# legacy-main.net
KiCad netlist of a schematic drawn in Altium Designer
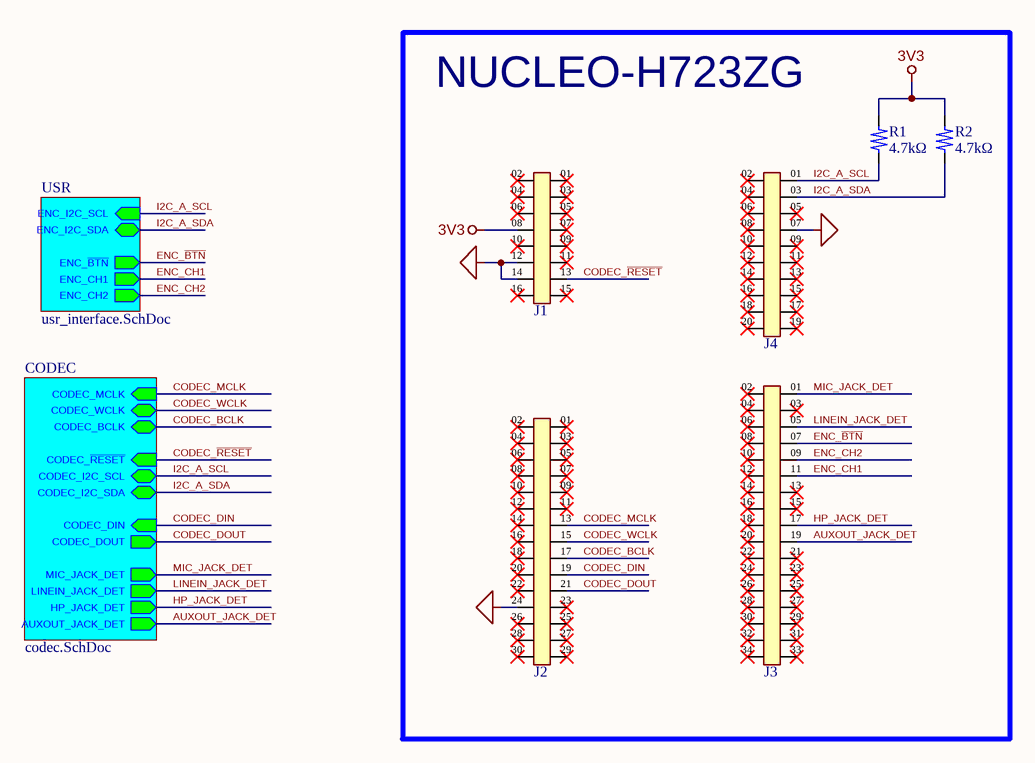
[diagram p0: legacy-main.SchDoc]

(export (version "E")
  (design (tool "Eeschema 10.0.6"))
  (components
    (comp (ref "J1")
      (value "TSW-108-07-G-D")
      (footprint "SAMTEC_TSW-108-07-G-D")
      (description "Pin Header, Unshrouded, Board-to-Board, 2.54 mm, 2 Rows, 16 Contacts, Through Hole, TSW")
      (libsource (lib "Connectors") (part "TSW-108-07-G-D"))
    )
    (comp (ref "J2")
      (value "TSW-115-07-G-D")
      (footprint "SAMTEC_TSW-115-07-G-D")
      (description "Conn, Header, 30Pos, 2Row, 2.54Mm Rohs Compliant: Yes ¦Samtec, Inc. TSW-115-07-G-D")
      (libsource (lib "Connectors") (part "TSW-115-07-G-D"))
    )
    (comp (ref "J3")
      (value "TSW-117-07-G-D-LL")
      (footprint "SAMTEC_TSW-117-07-G-D-LL")
      (description "Pin Header, Board-to-Board, 2.54 mm, 2 Rows, 34 Contacts, Through Hole, TSW Series")
      (libsource (lib "Connectors") (part "TSW-117-07-G-D-LL"))
    )
    (comp (ref "J4")
      (value "TSW-110-07-G-D")
      (footprint "SAMTEC_TSW-110-07-G-D")
      (description "Pin Header, Vertical, Board-to-Board, 2.54 mm, 2 Rows, 20 Contacts, Through Hole, HTSW Series")
      (libsource (lib "Connectors") (part "TSW-110-07-G-D"))
    )
    (comp (ref "R1")
      (value "4.7kΩ")
      (footprint "RESC2012")
      (description "125Mw Thick Film Resistors 100Ppm/ 1% 4.7K 0805 Chip Resistor Surface Mount Rohs")
      (fields
        (field (name "MANUFACTURER") "YAGEO")
        (field (name "MANUFACTURER PART NUMBER") "RC0805FR-074K7L")
      )
      (libsource (lib "Resistors") (part "RC0805FR-074K7L"))
    )
    (comp (ref "R2")
      (value "4.7kΩ")
      (footprint "RESC2012")
      (description "125Mw Thick Film Resistors 100Ppm/ 1% 4.7K 0805 Chip Resistor Surface Mount Rohs")
      (fields
        (field (name "MANUFACTURER") "YAGEO")
        (field (name "MANUFACTURER PART NUMBER") "RC0805FR-074K7L")
      )
      (libsource (lib "Resistors") (part "RC0805FR-074K7L"))
    )
  )
  (nets
    (net (code "1") (name "/AUXOUT_JACK_DET") (class "Default")
      (node (ref "J3") (pin "19") (pinfunction "19_19") (pintype "passive"))
    )
    (net (code "2") (name "/CODEC_BCLK") (class "Default")
      (node (ref "J2") (pin "17") (pinfunction "17_17") (pintype "passive"))
    )
    (net (code "3") (name "/CODEC_DIN") (class "Default")
      (node (ref "J2") (pin "19") (pinfunction "19_19") (pintype "passive"))
    )
    (net (code "4") (name "/CODEC_DOUT") (class "Default")
      (node (ref "J2") (pin "21") (pinfunction "21_21") (pintype "passive"))
    )
    (net (code "5") (name "/CODEC_MCLK") (class "Default")
      (node (ref "J2") (pin "13") (pinfunction "13_13") (pintype "passive"))
    )
    (net (code "6") (name "/CODEC_WCLK") (class "Default")
      (node (ref "J2") (pin "15") (pinfunction "15_15") (pintype "passive"))
    )
    (net (code "7") (name "/CODEC_~{RESET}") (class "Default")
      (node (ref "J1") (pin "13") (pinfunction "13_13") (pintype "passive"))
    )
    (net (code "8") (name "/ENC_CH1") (class "Default")
      (node (ref "J3") (pin "11") (pinfunction "11_11") (pintype "passive"))
    )
    (net (code "9") (name "/ENC_CH2") (class "Default")
      (node (ref "J3") (pin "09") (pinfunction "09_09") (pintype "passive"))
    )
    (net (code "10") (name "/ENC_~{BTN}") (class "Default")
      (node (ref "J3") (pin "07") (pinfunction "07_07") (pintype "passive"))
    )
    (net (code "11") (name "/HP_JACK_DET") (class "Default")
      (node (ref "J3") (pin "17") (pinfunction "17_17") (pintype "passive"))
    )
    (net (code "12") (name "/I2C_A_SCL") (class "Default")
      (node (ref "J4") (pin "01") (pinfunction "01_01") (pintype "passive"))
      (node (ref "R1") (pin "1") (pinfunction "1_1") (pintype "passive"))
    )
    (net (code "13") (name "/I2C_A_SDA") (class "Default")
      (node (ref "J4") (pin "03") (pinfunction "03_03") (pintype "passive"))
      (node (ref "R2") (pin "1") (pinfunction "1_1") (pintype "passive"))
    )
    (net (code "14") (name "/LINEIN_JACK_DET") (class "Default")
      (node (ref "J3") (pin "05") (pinfunction "05_05") (pintype "passive"))
    )
    (net (code "15") (name "/MIC_JACK_DET") (class "Default")
      (node (ref "J3") (pin "01") (pinfunction "01_01") (pintype "passive"))
    )
    (net (code "16") (name "3V3") (class "Default")
      (node (ref "J1") (pin "08") (pinfunction "08_08") (pintype "passive"))
      (node (ref "R1") (pin "2") (pinfunction "2_2") (pintype "passive"))
      (node (ref "R2") (pin "2") (pinfunction "2_2") (pintype "passive"))
    )
    (net (code "17") (name "DGND") (class "Default")
      (node (ref "J1") (pin "12") (pinfunction "12_12") (pintype "passive"))
      (node (ref "J1") (pin "14") (pinfunction "14_14") (pintype "passive"))
      (node (ref "J2") (pin "24") (pinfunction "24_24") (pintype "passive"))
      (node (ref "J4") (pin "07") (pinfunction "07_07") (pintype "passive"))
    )
    (net (code "18") (name "unconnected-(J1-Pad01)") (class "Default")
      (node (ref "J1") (pin "01") (pinfunction "01_01") (pintype "passive+no_connect"))
    )
    (net (code "19") (name "unconnected-(J1-Pad02)") (class "Default")
      (node (ref "J1") (pin "02") (pinfunction "02_02") (pintype "passive+no_connect"))
    )
    (net (code "20") (name "unconnected-(J1-Pad03)") (class "Default")
      (node (ref "J1") (pin "03") (pinfunction "03_03") (pintype "passive+no_connect"))
    )
    (net (code "21") (name "unconnected-(J1-Pad04)") (class "Default")
      (node (ref "J1") (pin "04") (pinfunction "04_04") (pintype "passive+no_connect"))
    )
    (net (code "22") (name "unconnected-(J1-Pad05)") (class "Default")
      (node (ref "J1") (pin "05") (pinfunction "05_05") (pintype "passive+no_connect"))
    )
    (net (code "23") (name "unconnected-(J1-Pad06)") (class "Default")
      (node (ref "J1") (pin "06") (pinfunction "06_06") (pintype "passive+no_connect"))
    )
    (net (code "24") (name "unconnected-(J1-Pad07)") (class "Default")
      (node (ref "J1") (pin "07") (pinfunction "07_07") (pintype "passive+no_connect"))
    )
    (net (code "25") (name "unconnected-(J1-Pad09)") (class "Default")
      (node (ref "J1") (pin "09") (pinfunction "09_09") (pintype "passive+no_connect"))
    )
    (net (code "26") (name "unconnected-(J1-Pad10)") (class "Default")
      (node (ref "J1") (pin "10") (pinfunction "10_10") (pintype "passive+no_connect"))
    )
    (net (code "27") (name "unconnected-(J1-Pad11)") (class "Default")
      (node (ref "J1") (pin "11") (pinfunction "11_11") (pintype "passive+no_connect"))
    )
    (net (code "28") (name "unconnected-(J1-Pad15)") (class "Default")
      (node (ref "J1") (pin "15") (pinfunction "15_15") (pintype "passive+no_connect"))
    )
    (net (code "29") (name "unconnected-(J1-Pad16)") (class "Default")
      (node (ref "J1") (pin "16") (pinfunction "16_16") (pintype "passive+no_connect"))
    )
    (net (code "30") (name "unconnected-(J2-Pad01)") (class "Default")
      (node (ref "J2") (pin "01") (pinfunction "01_01") (pintype "passive+no_connect"))
    )
    (net (code "31") (name "unconnected-(J2-Pad02)") (class "Default")
      (node (ref "J2") (pin "02") (pinfunction "02_02") (pintype "passive+no_connect"))
    )
    (net (code "32") (name "unconnected-(J2-Pad03)") (class "Default")
      (node (ref "J2") (pin "03") (pinfunction "03_03") (pintype "passive+no_connect"))
    )
    (net (code "33") (name "unconnected-(J2-Pad04)") (class "Default")
      (node (ref "J2") (pin "04") (pinfunction "04_04") (pintype "passive+no_connect"))
    )
    (net (code "34") (name "unconnected-(J2-Pad05)") (class "Default")
      (node (ref "J2") (pin "05") (pinfunction "05_05") (pintype "passive+no_connect"))
    )
    (net (code "35") (name "unconnected-(J2-Pad06)") (class "Default")
      (node (ref "J2") (pin "06") (pinfunction "06_06") (pintype "passive+no_connect"))
    )
    (net (code "36") (name "unconnected-(J2-Pad07)") (class "Default")
      (node (ref "J2") (pin "07") (pinfunction "07_07") (pintype "passive+no_connect"))
    )
    (net (code "37") (name "unconnected-(J2-Pad08)") (class "Default")
      (node (ref "J2") (pin "08") (pinfunction "08_08") (pintype "passive+no_connect"))
    )
    (net (code "38") (name "unconnected-(J2-Pad09)") (class "Default")
      (node (ref "J2") (pin "09") (pinfunction "09_09") (pintype "passive+no_connect"))
    )
    (net (code "39") (name "unconnected-(J2-Pad10)") (class "Default")
      (node (ref "J2") (pin "10") (pinfunction "10_10") (pintype "passive+no_connect"))
    )
    (net (code "40") (name "unconnected-(J2-Pad11)") (class "Default")
      (node (ref "J2") (pin "11") (pinfunction "11_11") (pintype "passive+no_connect"))
    )
    (net (code "41") (name "unconnected-(J2-Pad12)") (class "Default")
      (node (ref "J2") (pin "12") (pinfunction "12_12") (pintype "passive+no_connect"))
    )
    (net (code "42") (name "unconnected-(J2-Pad14)") (class "Default")
      (node (ref "J2") (pin "14") (pinfunction "14_14") (pintype "passive+no_connect"))
    )
    (net (code "43") (name "unconnected-(J2-Pad16)") (class "Default")
      (node (ref "J2") (pin "16") (pinfunction "16_16") (pintype "passive+no_connect"))
    )
    (net (code "44") (name "unconnected-(J2-Pad18)") (class "Default")
      (node (ref "J2") (pin "18") (pinfunction "18_18") (pintype "passive+no_connect"))
    )
    (net (code "45") (name "unconnected-(J2-Pad20)") (class "Default")
      (node (ref "J2") (pin "20") (pinfunction "20_20") (pintype "passive+no_connect"))
    )
    (net (code "46") (name "unconnected-(J2-Pad22)") (class "Default")
      (node (ref "J2") (pin "22") (pinfunction "22_22") (pintype "passive+no_connect"))
    )
    (net (code "47") (name "unconnected-(J2-Pad23)") (class "Default")
      (node (ref "J2") (pin "23") (pinfunction "23_23") (pintype "passive+no_connect"))
    )
    (net (code "48") (name "unconnected-(J2-Pad25)") (class "Default")
      (node (ref "J2") (pin "25") (pinfunction "25_25") (pintype "passive+no_connect"))
    )
    (net (code "49") (name "unconnected-(J2-Pad26)") (class "Default")
      (node (ref "J2") (pin "26") (pinfunction "26_26") (pintype "passive+no_connect"))
    )
    (net (code "50") (name "unconnected-(J2-Pad27)") (class "Default")
      (node (ref "J2") (pin "27") (pinfunction "27_27") (pintype "passive+no_connect"))
    )
    (net (code "51") (name "unconnected-(J2-Pad28)") (class "Default")
      (node (ref "J2") (pin "28") (pinfunction "28_28") (pintype "passive+no_connect"))
    )
    (net (code "52") (name "unconnected-(J2-Pad29)") (class "Default")
      (node (ref "J2") (pin "29") (pinfunction "29_29") (pintype "passive+no_connect"))
    )
    (net (code "53") (name "unconnected-(J2-Pad30)") (class "Default")
      (node (ref "J2") (pin "30") (pinfunction "30_30") (pintype "passive+no_connect"))
    )
    (net (code "54") (name "unconnected-(J3-Pad02)") (class "Default")
      (node (ref "J3") (pin "02") (pinfunction "02_02") (pintype "passive+no_connect"))
    )
    (net (code "55") (name "unconnected-(J3-Pad03)") (class "Default")
      (node (ref "J3") (pin "03") (pinfunction "03_03") (pintype "passive+no_connect"))
    )
    (net (code "56") (name "unconnected-(J3-Pad04)") (class "Default")
      (node (ref "J3") (pin "04") (pinfunction "04_04") (pintype "passive+no_connect"))
    )
    (net (code "57") (name "unconnected-(J3-Pad06)") (class "Default")
      (node (ref "J3") (pin "06") (pinfunction "06_06") (pintype "passive+no_connect"))
    )
    (net (code "58") (name "unconnected-(J3-Pad08)") (class "Default")
      (node (ref "J3") (pin "08") (pinfunction "08_08") (pintype "passive+no_connect"))
    )
    (net (code "59") (name "unconnected-(J3-Pad10)") (class "Default")
      (node (ref "J3") (pin "10") (pinfunction "10_10") (pintype "passive+no_connect"))
    )
    (net (code "60") (name "unconnected-(J3-Pad12)") (class "Default")
      (node (ref "J3") (pin "12") (pinfunction "12_12") (pintype "passive+no_connect"))
    )
    (net (code "61") (name "unconnected-(J3-Pad13)") (class "Default")
      (node (ref "J3") (pin "13") (pinfunction "13_13") (pintype "passive+no_connect"))
    )
    (net (code "62") (name "unconnected-(J3-Pad14)") (class "Default")
      (node (ref "J3") (pin "14") (pinfunction "14_14") (pintype "passive+no_connect"))
    )
    (net (code "63") (name "unconnected-(J3-Pad15)") (class "Default")
      (node (ref "J3") (pin "15") (pinfunction "15_15") (pintype "passive+no_connect"))
    )
    (net (code "64") (name "unconnected-(J3-Pad16)") (class "Default")
      (node (ref "J3") (pin "16") (pinfunction "16_16") (pintype "passive+no_connect"))
    )
    (net (code "65") (name "unconnected-(J3-Pad18)") (class "Default")
      (node (ref "J3") (pin "18") (pinfunction "18_18") (pintype "passive+no_connect"))
    )
    (net (code "66") (name "unconnected-(J3-Pad20)") (class "Default")
      (node (ref "J3") (pin "20") (pinfunction "20_20") (pintype "passive+no_connect"))
    )
    (net (code "67") (name "unconnected-(J3-Pad21)") (class "Default")
      (node (ref "J3") (pin "21") (pinfunction "21_21") (pintype "passive+no_connect"))
    )
    (net (code "68") (name "unconnected-(J3-Pad22)") (class "Default")
      (node (ref "J3") (pin "22") (pinfunction "22_22") (pintype "passive+no_connect"))
    )
    (net (code "69") (name "unconnected-(J3-Pad23)") (class "Default")
      (node (ref "J3") (pin "23") (pinfunction "23_23") (pintype "passive+no_connect"))
    )
    (net (code "70") (name "unconnected-(J3-Pad24)") (class "Default")
      (node (ref "J3") (pin "24") (pinfunction "24_24") (pintype "passive+no_connect"))
    )
    (net (code "71") (name "unconnected-(J3-Pad25)") (class "Default")
      (node (ref "J3") (pin "25") (pinfunction "25_25") (pintype "passive+no_connect"))
    )
    (net (code "72") (name "unconnected-(J3-Pad26)") (class "Default")
      (node (ref "J3") (pin "26") (pinfunction "26_26") (pintype "passive+no_connect"))
    )
    (net (code "73") (name "unconnected-(J3-Pad27)") (class "Default")
      (node (ref "J3") (pin "27") (pinfunction "27_27") (pintype "passive+no_connect"))
    )
    (net (code "74") (name "unconnected-(J3-Pad28)") (class "Default")
      (node (ref "J3") (pin "28") (pinfunction "28_28") (pintype "passive+no_connect"))
    )
    (net (code "75") (name "unconnected-(J3-Pad29)") (class "Default")
      (node (ref "J3") (pin "29") (pinfunction "29_29") (pintype "passive+no_connect"))
    )
    (net (code "76") (name "unconnected-(J3-Pad30)") (class "Default")
      (node (ref "J3") (pin "30") (pinfunction "30_30") (pintype "passive+no_connect"))
    )
    (net (code "77") (name "unconnected-(J3-Pad31)") (class "Default")
      (node (ref "J3") (pin "31") (pinfunction "31_31") (pintype "passive+no_connect"))
    )
    (net (code "78") (name "unconnected-(J3-Pad32)") (class "Default")
      (node (ref "J3") (pin "32") (pinfunction "32_32") (pintype "passive+no_connect"))
    )
    (net (code "79") (name "unconnected-(J3-Pad33)") (class "Default")
      (node (ref "J3") (pin "33") (pinfunction "33_33") (pintype "passive+no_connect"))
    )
    (net (code "80") (name "unconnected-(J3-Pad34)") (class "Default")
      (node (ref "J3") (pin "34") (pinfunction "34_34") (pintype "passive+no_connect"))
    )
    (net (code "81") (name "unconnected-(J4-Pad02)") (class "Default")
      (node (ref "J4") (pin "02") (pinfunction "02_02") (pintype "passive+no_connect"))
    )
    (net (code "82") (name "unconnected-(J4-Pad04)") (class "Default")
      (node (ref "J4") (pin "04") (pinfunction "04_04") (pintype "passive+no_connect"))
    )
    (net (code "83") (name "unconnected-(J4-Pad05)") (class "Default")
      (node (ref "J4") (pin "05") (pinfunction "05_05") (pintype "passive+no_connect"))
    )
    (net (code "84") (name "unconnected-(J4-Pad06)") (class "Default")
      (node (ref "J4") (pin "06") (pinfunction "06_06") (pintype "passive+no_connect"))
    )
    (net (code "85") (name "unconnected-(J4-Pad08)") (class "Default")
      (node (ref "J4") (pin "08") (pinfunction "08_08") (pintype "passive+no_connect"))
    )
    (net (code "86") (name "unconnected-(J4-Pad09)") (class "Default")
      (node (ref "J4") (pin "09") (pinfunction "09_09") (pintype "passive+no_connect"))
    )
    (net (code "87") (name "unconnected-(J4-Pad10)") (class "Default")
      (node (ref "J4") (pin "10") (pinfunction "10_10") (pintype "passive+no_connect"))
    )
    (net (code "88") (name "unconnected-(J4-Pad11)") (class "Default")
      (node (ref "J4") (pin "11") (pinfunction "11_11") (pintype "passive+no_connect"))
    )
    (net (code "89") (name "unconnected-(J4-Pad12)") (class "Default")
      (node (ref "J4") (pin "12") (pinfunction "12_12") (pintype "passive+no_connect"))
    )
    (net (code "90") (name "unconnected-(J4-Pad13)") (class "Default")
      (node (ref "J4") (pin "13") (pinfunction "13_13") (pintype "passive+no_connect"))
    )
    (net (code "91") (name "unconnected-(J4-Pad14)") (class "Default")
      (node (ref "J4") (pin "14") (pinfunction "14_14") (pintype "passive+no_connect"))
    )
    (net (code "92") (name "unconnected-(J4-Pad15)") (class "Default")
      (node (ref "J4") (pin "15") (pinfunction "15_15") (pintype "passive+no_connect"))
    )
    (net (code "93") (name "unconnected-(J4-Pad16)") (class "Default")
      (node (ref "J4") (pin "16") (pinfunction "16_16") (pintype "passive+no_connect"))
    )
    (net (code "94") (name "unconnected-(J4-Pad17)") (class "Default")
      (node (ref "J4") (pin "17") (pinfunction "17_17") (pintype "passive+no_connect"))
    )
    (net (code "95") (name "unconnected-(J4-Pad18)") (class "Default")
      (node (ref "J4") (pin "18") (pinfunction "18_18") (pintype "passive+no_connect"))
    )
    (net (code "96") (name "unconnected-(J4-Pad19)") (class "Default")
      (node (ref "J4") (pin "19") (pinfunction "19_19") (pintype "passive+no_connect"))
    )
    (net (code "97") (name "unconnected-(J4-Pad20)") (class "Default")
      (node (ref "J4") (pin "20") (pinfunction "20_20") (pintype "passive+no_connect"))
    )
  )
)
